# dc25-darknet-dialer-eaglev8_3.net
KiCad netlist of a schematic drawn in EAGLE
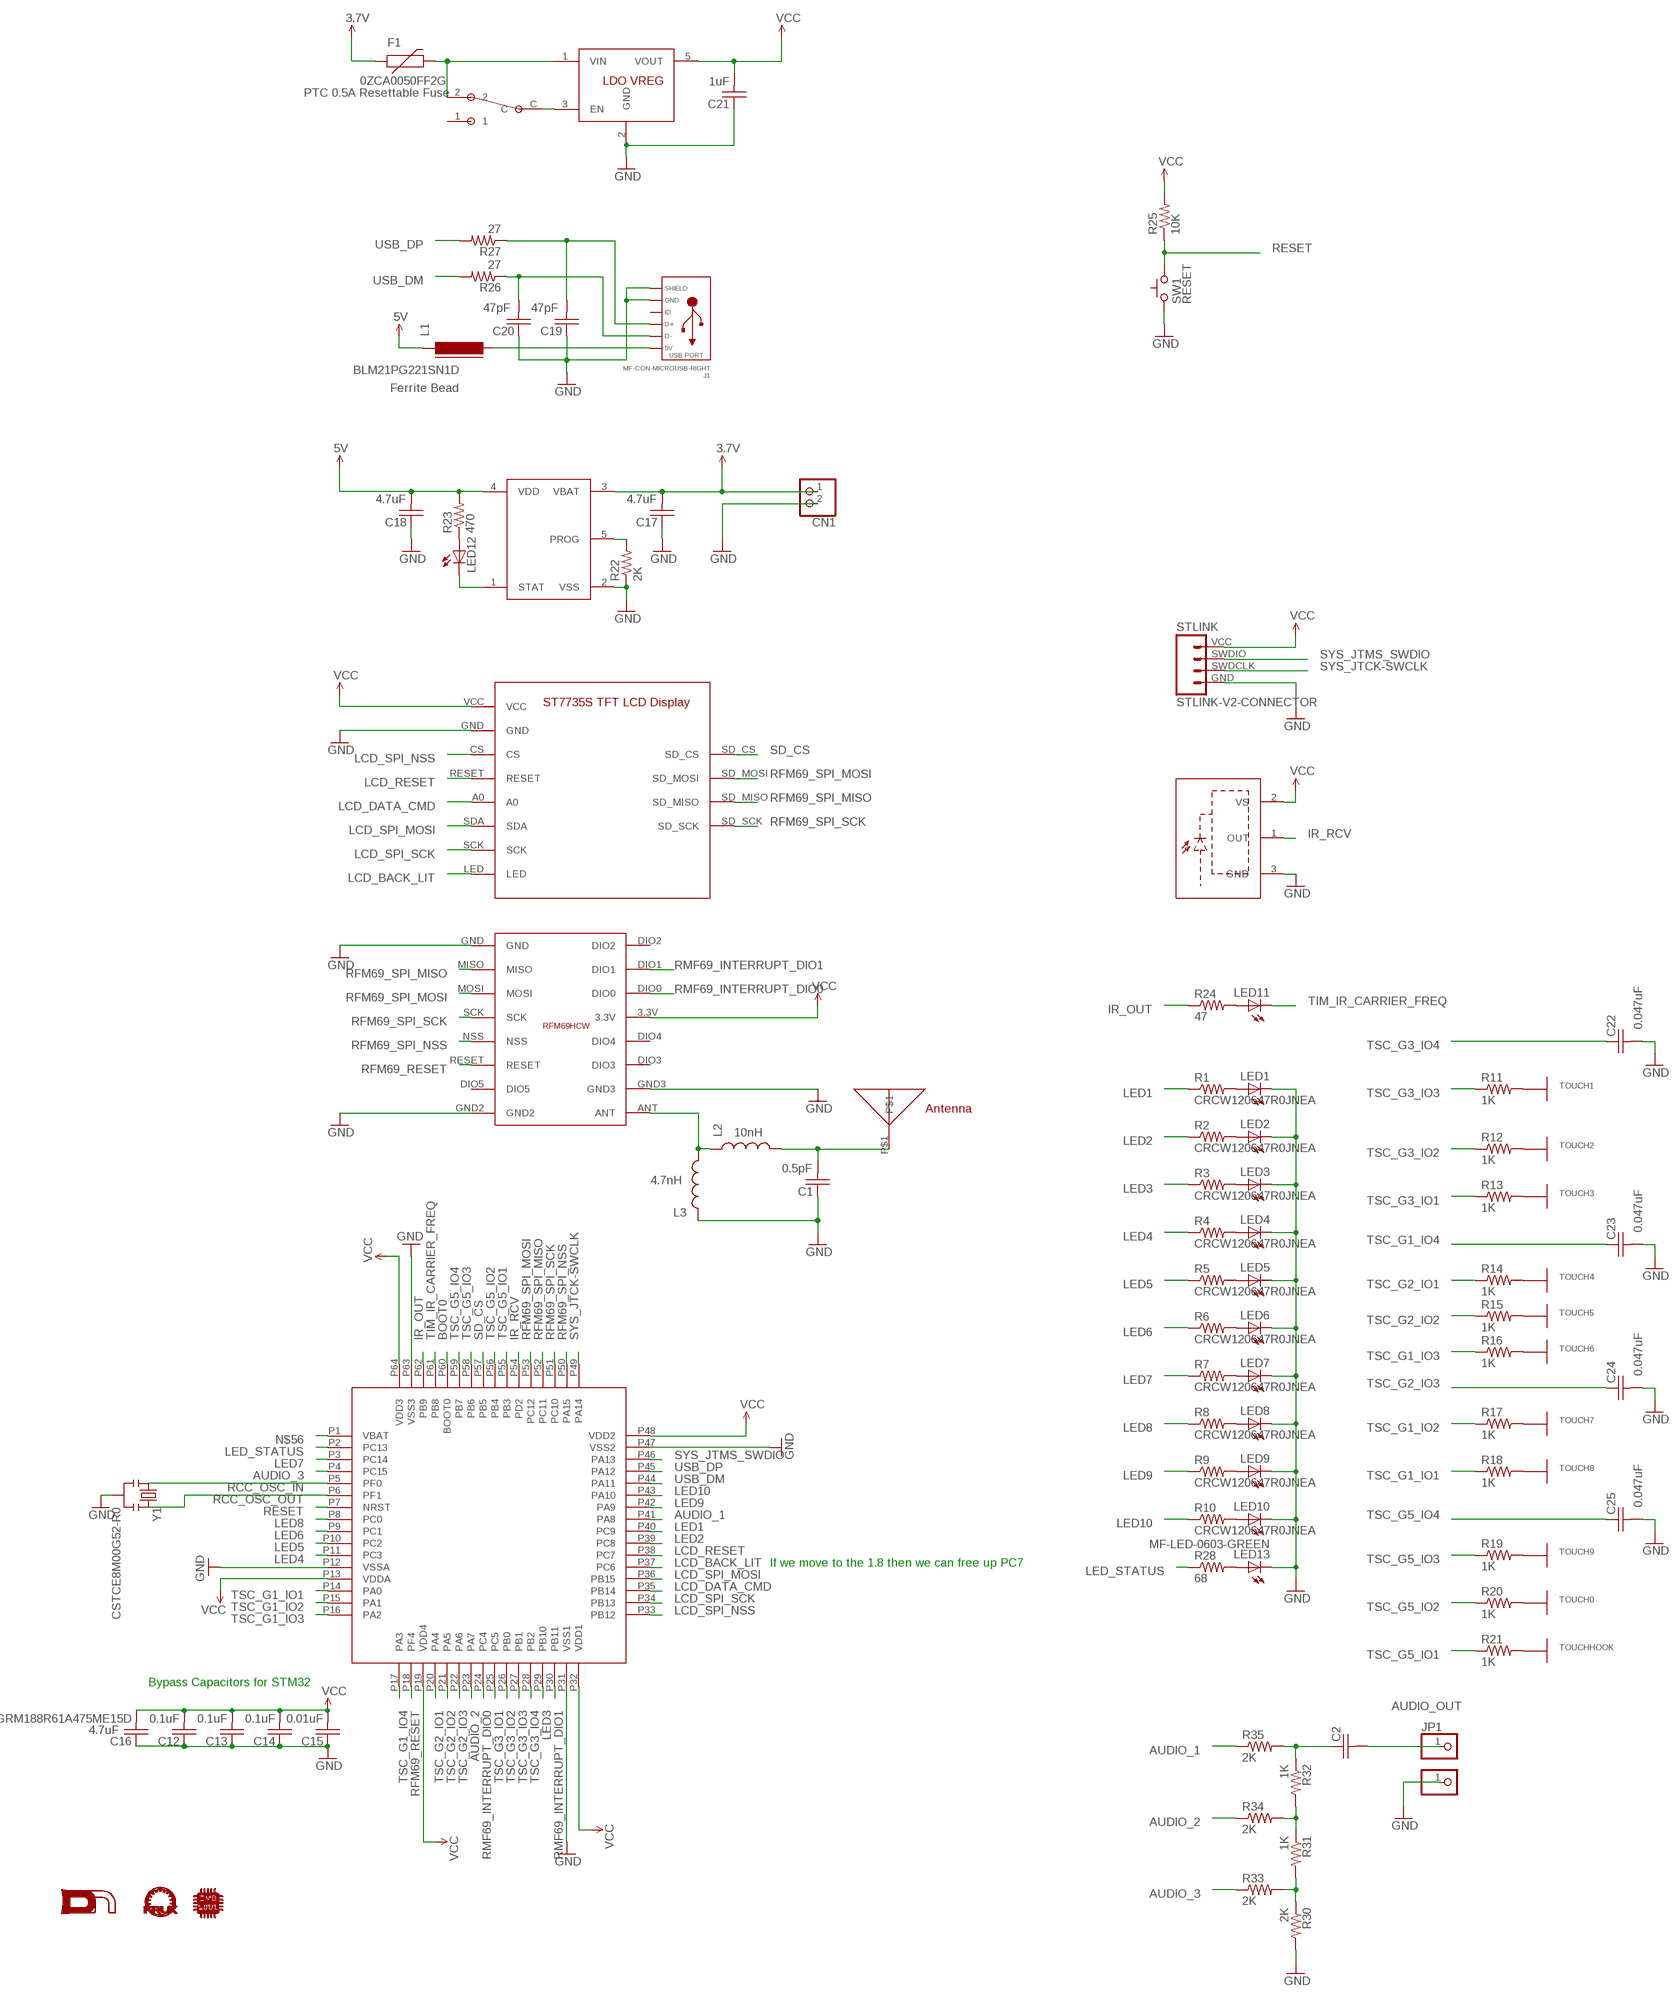
[diagram p0: schematic, sheet 1]

(export (version "E")
  (design (tool "Eeschema 10.0.6"))
  (components
    (comp (ref "C1")
      (value "251R14S0R5BV4T")
      (footprint "eagle-import:C0603")
      (libsource (lib "eagle-import") (part "C-USC0603"))
    )
    (comp (ref "C2")
      (value "GRM188C80G106ME47D")
      (footprint "eagle-import:C0603")
      (libsource (lib "eagle-import") (part "C-USC0603"))
    )
    (comp (ref "C12")
      (value "0.1uF")
      (footprint "eagle-import:C0603")
      (libsource (lib "eagle-import") (part "C-USC0603"))
    )
    (comp (ref "C13")
      (value "0.1uF")
      (footprint "eagle-import:C0603")
      (libsource (lib "eagle-import") (part "C-USC0603"))
    )
    (comp (ref "C14")
      (value "0.1uF")
      (footprint "eagle-import:C0603")
      (libsource (lib "eagle-import") (part "C-USC0603"))
    )
    (comp (ref "C15")
      (value "0.01uF")
      (footprint "eagle-import:C0603")
      (libsource (lib "eagle-import") (part "C-USC0603"))
    )
    (comp (ref "C16")
      (value "GRM188R61A475ME15D")
      (footprint "eagle-import:C0603")
      (libsource (lib "eagle-import") (part "C-USC0603"))
    )
    (comp (ref "C17")
      (value "GRM188R61A475ME15D")
      (footprint "eagle-import:C0603")
      (libsource (lib "eagle-import") (part "C-USC0603"))
    )
    (comp (ref "C18")
      (value "GRM188R61A475ME15D")
      (footprint "eagle-import:C0603")
      (libsource (lib "eagle-import") (part "C-USC0603"))
    )
    (comp (ref "C19")
      (value "C0603C470J3GACTU")
      (footprint "eagle-import:C0603")
      (libsource (lib "eagle-import") (part "C-USC0603"))
    )
    (comp (ref "C20")
      (value "C0603C470J3GACTU")
      (footprint "eagle-import:C0603")
      (libsource (lib "eagle-import") (part "C-USC0603"))
    )
    (comp (ref "C21")
      (value "1uF")
      (footprint "eagle-import:C0603")
      (libsource (lib "eagle-import") (part "C-USC0603"))
    )
    (comp (ref "C22")
      (value "C0603C473J3RACAUTO")
      (footprint "eagle-import:C0603")
      (libsource (lib "eagle-import") (part "C-USC0603"))
    )
    (comp (ref "C23")
      (value "C0603C473J3RACAUTO")
      (footprint "eagle-import:C0603")
      (libsource (lib "eagle-import") (part "C-USC0603"))
    )
    (comp (ref "C24")
      (value "C0603C473J3RACAUTO")
      (footprint "eagle-import:C0603")
      (libsource (lib "eagle-import") (part "C-USC0603"))
    )
    (comp (ref "C25")
      (value "C0603C473J3RACAUTO")
      (footprint "eagle-import:C0603")
      (libsource (lib "eagle-import") (part "C-USC0603"))
    )
    (comp (ref "CN1")
      (value "JST_2PIN-THM-RA")
      (footprint "eagle-import:JST-PH-2-THM-RA")
      (libsource (lib "eagle-import") (part "JST_2PIN-THM-RA"))
    )
    (comp (ref "F1")
      (value "0ZCA0050FF2G")
      (footprint "eagle-import:PTC-1206")
      (libsource (lib "eagle-import") (part "PTCSMD"))
    )
    (comp (ref "J1")
      (value "MF-CON-MICROUSB-RIGHT")
      (footprint "eagle-import:MICROUSB-RIGHT")
      (fields (field (name "HOUSEPART") "YES"))
      (libsource (lib "eagle-import") (part "USB_MICRO_RIGHT"))
    )
    (comp (ref "JP1")
      (value "PINHD-1X1CB")
      (footprint "eagle-import:1X01-CLEANBIG")
      (libsource (lib "eagle-import") (part "PINHD-1X1CB"))
    )
    (comp (ref "JP2")
      (value "PINHD-1X1CB")
      (footprint "eagle-import:1X01-CLEANBIG")
      (libsource (lib "eagle-import") (part "PINHD-1X1CB"))
    )
    (comp (ref "L1")
      (value "BLM21PG221SN1D")
      (footprint "eagle-import:FB603")
      (libsource (lib "eagle-import") (part "FERRITE-0603"))
    )
    (comp (ref "L2")
      (value "CI160808-10NJ")
      (footprint "eagle-import:0603")
      (libsource (lib "eagle-import") (part "INDUCTOR0603"))
    )
    (comp (ref "L3")
      (value "CI160808-4N7D")
      (footprint "eagle-import:0603")
      (libsource (lib "eagle-import") (part "INDUCTOR0603"))
    )
    (comp (ref "LED1")
      (value "LEDREVERSEMOUNT_NOPASTE")
      (footprint "eagle-import:GULLWING_LED_NOPASTE")
      (libsource (lib "eagle-import") (part "LEDREVERSEMOUNT_NOPASTE"))
    )
    (comp (ref "LED2")
      (value "LEDREVERSEMOUNT_NOPASTE")
      (footprint "eagle-import:GULLWING_LED_NOPASTE")
      (libsource (lib "eagle-import") (part "LEDREVERSEMOUNT_NOPASTE"))
    )
    (comp (ref "LED3")
      (value "LEDREVERSEMOUNT_NOPASTE")
      (footprint "eagle-import:GULLWING_LED_NOPASTE")
      (libsource (lib "eagle-import") (part "LEDREVERSEMOUNT_NOPASTE"))
    )
    (comp (ref "LED4")
      (value "LEDREVERSEMOUNT_NOPASTE")
      (footprint "eagle-import:GULLWING_LED_NOPASTE")
      (libsource (lib "eagle-import") (part "LEDREVERSEMOUNT_NOPASTE"))
    )
    (comp (ref "LED5")
      (value "LEDREVERSEMOUNT_NOPASTE")
      (footprint "eagle-import:GULLWING_LED_NOPASTE")
      (libsource (lib "eagle-import") (part "LEDREVERSEMOUNT_NOPASTE"))
    )
    (comp (ref "LED6")
      (value "LEDREVERSEMOUNT_NOPASTE")
      (footprint "eagle-import:GULLWING_LED_NOPASTE")
      (libsource (lib "eagle-import") (part "LEDREVERSEMOUNT_NOPASTE"))
    )
    (comp (ref "LED7")
      (value "LEDREVERSEMOUNT_NOPASTE")
      (footprint "eagle-import:GULLWING_LED_NOPASTE")
      (libsource (lib "eagle-import") (part "LEDREVERSEMOUNT_NOPASTE"))
    )
    (comp (ref "LED8")
      (value "LEDREVERSEMOUNT_NOPASTE")
      (footprint "eagle-import:GULLWING_LED_NOPASTE")
      (libsource (lib "eagle-import") (part "LEDREVERSEMOUNT_NOPASTE"))
    )
    (comp (ref "LED9")
      (value "LEDREVERSEMOUNT_NOPASTE")
      (footprint "eagle-import:GULLWING_LED_NOPASTE")
      (libsource (lib "eagle-import") (part "LEDREVERSEMOUNT_NOPASTE"))
    )
    (comp (ref "LED10")
      (value "LEDREVERSEMOUNT_NOPASTE")
      (footprint "eagle-import:GULLWING_LED_NOPASTE")
      (libsource (lib "eagle-import") (part "LEDREVERSEMOUNT_NOPASTE"))
    )
    (comp (ref "LED11")
      (value "LED5MM")
      (footprint "eagle-import:LED5MM")
      (libsource (lib "eagle-import") (part "LED5MM"))
    )
    (comp (ref "LED12")
      (value "MF-LED-0603-GREEN")
      (footprint "eagle-import:LED-0603")
      (libsource (lib "eagle-import") (part "LED0603"))
    )
    (comp (ref "LED13")
      (value "MF-LED-0603-GREEN")
      (footprint "eagle-import:LED-0603")
      (libsource (lib "eagle-import") (part "LED0603"))
    )
    (comp (ref "R1")
      (value "CRCW120647R0JNEA")
      (footprint "eagle-import:1206")
      (libsource (lib "eagle-import") (part "RESISTOR1206"))
    )
    (comp (ref "R2")
      (value "CRCW120647R0JNEA")
      (footprint "eagle-import:1206")
      (libsource (lib "eagle-import") (part "RESISTOR1206"))
    )
    (comp (ref "R3")
      (value "CRCW120647R0JNEA")
      (footprint "eagle-import:1206")
      (libsource (lib "eagle-import") (part "RESISTOR1206"))
    )
    (comp (ref "R4")
      (value "CRCW120647R0JNEA")
      (footprint "eagle-import:1206")
      (libsource (lib "eagle-import") (part "RESISTOR1206"))
    )
    (comp (ref "R5")
      (value "CRCW120647R0JNEA")
      (footprint "eagle-import:1206")
      (libsource (lib "eagle-import") (part "RESISTOR1206"))
    )
    (comp (ref "R6")
      (value "CRCW120647R0JNEA")
      (footprint "eagle-import:1206")
      (libsource (lib "eagle-import") (part "RESISTOR1206"))
    )
    (comp (ref "R7")
      (value "CRCW120647R0JNEA")
      (footprint "eagle-import:1206")
      (libsource (lib "eagle-import") (part "RESISTOR1206"))
    )
    (comp (ref "R8")
      (value "CRCW120647R0JNEA")
      (footprint "eagle-import:1206")
      (libsource (lib "eagle-import") (part "RESISTOR1206"))
    )
    (comp (ref "R9")
      (value "CRCW120647R0JNEA")
      (footprint "eagle-import:1206")
      (libsource (lib "eagle-import") (part "RESISTOR1206"))
    )
    (comp (ref "R10")
      (value "CRCW120647R0JNEA")
      (footprint "eagle-import:1206")
      (libsource (lib "eagle-import") (part "RESISTOR1206"))
    )
    (comp (ref "R11")
      (value "1K")
      (footprint "eagle-import:0603-RES")
      (libsource (lib "eagle-import") (part "RESISTOR0603-RES"))
    )
    (comp (ref "R12")
      (value "1K")
      (footprint "eagle-import:0603-RES")
      (libsource (lib "eagle-import") (part "RESISTOR0603-RES"))
    )
    (comp (ref "R13")
      (value "1K")
      (footprint "eagle-import:0603-RES")
      (libsource (lib "eagle-import") (part "RESISTOR0603-RES"))
    )
    (comp (ref "R14")
      (value "1K")
      (footprint "eagle-import:0603-RES")
      (libsource (lib "eagle-import") (part "RESISTOR0603-RES"))
    )
    (comp (ref "R15")
      (value "1K")
      (footprint "eagle-import:0603-RES")
      (libsource (lib "eagle-import") (part "RESISTOR0603-RES"))
    )
    (comp (ref "R16")
      (value "1K")
      (footprint "eagle-import:0603-RES")
      (libsource (lib "eagle-import") (part "RESISTOR0603-RES"))
    )
    (comp (ref "R17")
      (value "1K")
      (footprint "eagle-import:0603-RES")
      (libsource (lib "eagle-import") (part "RESISTOR0603-RES"))
    )
    (comp (ref "R18")
      (value "1K")
      (footprint "eagle-import:0603-RES")
      (libsource (lib "eagle-import") (part "RESISTOR0603-RES"))
    )
    (comp (ref "R19")
      (value "1K")
      (footprint "eagle-import:0603-RES")
      (libsource (lib "eagle-import") (part "RESISTOR0603-RES"))
    )
    (comp (ref "R20")
      (value "1K")
      (footprint "eagle-import:0603-RES")
      (libsource (lib "eagle-import") (part "RESISTOR0603-RES"))
    )
    (comp (ref "R21")
      (value "1K")
      (footprint "eagle-import:0603-RES")
      (libsource (lib "eagle-import") (part "RESISTOR0603-RES"))
    )
    (comp (ref "R22")
      (value "2K")
      (footprint "eagle-import:0603-RES")
      (libsource (lib "eagle-import") (part "RESISTOR0603-RES"))
    )
    (comp (ref "R23")
      (value "470")
      (footprint "eagle-import:0603-RES")
      (libsource (lib "eagle-import") (part "RESISTOR0603-RES"))
    )
    (comp (ref "R24")
      (value "47")
      (footprint "eagle-import:0207_7")
      (libsource (lib "eagle-import") (part "R-US_0207/7"))
    )
    (comp (ref "R25")
      (value "10K")
      (footprint "eagle-import:0603-RES")
      (libsource (lib "eagle-import") (part "RESISTOR0603-RES"))
    )
    (comp (ref "R26")
      (value "27")
      (footprint "eagle-import:0603-RES")
      (libsource (lib "eagle-import") (part "RESISTOR0603-RES"))
    )
    (comp (ref "R27")
      (value "27")
      (footprint "eagle-import:0603-RES")
      (libsource (lib "eagle-import") (part "RESISTOR0603-RES"))
    )
    (comp (ref "R28")
      (value "68")
      (footprint "eagle-import:0603-RES")
      (libsource (lib "eagle-import") (part "RESISTOR0603-RES"))
    )
    (comp (ref "R30")
      (value "2K")
      (footprint "eagle-import:0603-RES")
      (libsource (lib "eagle-import") (part "RESISTOR0603-RES"))
    )
    (comp (ref "R31")
      (value "1K")
      (footprint "eagle-import:0603-RES")
      (libsource (lib "eagle-import") (part "RESISTOR0603-RES"))
    )
    (comp (ref "R32")
      (value "1K")
      (footprint "eagle-import:0603-RES")
      (libsource (lib "eagle-import") (part "RESISTOR0603-RES"))
    )
    (comp (ref "R33")
      (value "2K")
      (footprint "eagle-import:0603-RES")
      (libsource (lib "eagle-import") (part "RESISTOR0603-RES"))
    )
    (comp (ref "R34")
      (value "2K")
      (footprint "eagle-import:0603-RES")
      (libsource (lib "eagle-import") (part "RESISTOR0603-RES"))
    )
    (comp (ref "R35")
      (value "2K")
      (footprint "eagle-import:0603-RES")
      (libsource (lib "eagle-import") (part "RESISTOR0603-RES"))
    )
    (comp (ref "STLINK")
      (value "STLINK-V2-CONNECTOR")
      (footprint "eagle-import:1X04")
      (libsource (lib "eagle-import") (part "STLINK-V2-CONNECTOR"))
    )
    (comp (ref "SW1")
      (value "RESET")
      (footprint "eagle-import:TACTILE-2PIN-NARROW")
      (libsource (lib "eagle-import") (part "SWITCH_TACTILETACTILE-2PIN-NARROW"))
    )
    (comp (ref "TOUCH0")
      (value "CAP_TOUCH0")
      (footprint "eagle-import:CAP_TOUCH_PAD_0")
      (libsource (lib "eagle-import") (part "CAP_TOUCH0"))
    )
    (comp (ref "TOUCH1")
      (value "CAP_TOUCH1")
      (footprint "eagle-import:CAP_TOUCH_PAD_1")
      (libsource (lib "eagle-import") (part "CAP_TOUCH1"))
    )
    (comp (ref "TOUCH2")
      (value "CAP_TOUCH2")
      (footprint "eagle-import:CAP_TOUCH_PAD_2")
      (libsource (lib "eagle-import") (part "CAP_TOUCH2"))
    )
    (comp (ref "TOUCH3")
      (value "CAP_TOUCH3")
      (footprint "eagle-import:CAP_TOUCH_PAD_3")
      (libsource (lib "eagle-import") (part "CAP_TOUCH3"))
    )
    (comp (ref "TOUCH4")
      (value "CAP_TOUCH4")
      (footprint "eagle-import:CAP_TOUCH_PAD_4")
      (libsource (lib "eagle-import") (part "CAP_TOUCH4"))
    )
    (comp (ref "TOUCH5")
      (value "CAP_TOUCH5")
      (footprint "eagle-import:CAP_TOUCH_PAD_5")
      (libsource (lib "eagle-import") (part "CAP_TOUCH5"))
    )
    (comp (ref "TOUCH6")
      (value "CAP_TOUCH6")
      (footprint "eagle-import:CAP_TOUCH_PAD_6")
      (libsource (lib "eagle-import") (part "CAP_TOUCH6"))
    )
    (comp (ref "TOUCH7")
      (value "CAP_TOUCH7")
      (footprint "eagle-import:CAP_TOUCH_PAD_7")
      (libsource (lib "eagle-import") (part "CAP_TOUCH7"))
    )
    (comp (ref "TOUCH8")
      (value "CAP_TOUCH8")
      (footprint "eagle-import:CAP_TOUCH_PAD_8")
      (libsource (lib "eagle-import") (part "CAP_TOUCH8"))
    )
    (comp (ref "TOUCH9")
      (value "CAP_TOUCH9")
      (footprint "eagle-import:CAP_TOUCH_PAD_9")
      (libsource (lib "eagle-import") (part "CAP_TOUCH9"))
    )
    (comp (ref "TOUCHHOOK")
      (value "CAP_TOUCHHOOK")
      (footprint "eagle-import:CAP_TOUCH_PAD_HOOK")
      (libsource (lib "eagle-import") (part "CAP_TOUCHHOOK"))
    )
    (comp (ref "U$1")
      (value "DN_LOGODC25")
      (footprint "eagle-import:DARKNET_LOGO_DC25")
      (libsource (lib "eagle-import") (part "DN_LOGODC25"))
    )
    (comp (ref "U$2")
      (value "STM32F302RBT6")
      (footprint "eagle-import:LQFP64")
      (libsource (lib "eagle-import") (part "STM32F302XC"))
    )
    (comp (ref "U$11")
      (value "SWITCH_SPDT")
      (footprint "eagle-import:SPDT_SSAJ120100")
      (libsource (lib "eagle-import") (part "SWITCH_SPDT"))
    )
    (comp (ref "U$12")
      (value "KRUX_LOGO")
      (footprint "eagle-import:KRUX_LOGO")
      (libsource (lib "eagle-import") (part "KRUX_LOGO"))
    )
    (comp (ref "U$15")
      (value "RFM69HCWRFM69HCWSMDNOPASTE")
      (footprint "eagle-import:16PIN-PCB-SMD-NOPASTE")
      (libsource (lib "eagle-import") (part "RFM69HCWRFM69HCWSMDNOPASTE"))
    )
    (comp (ref "U$21")
      (value "0915AT43A0026E")
      (footprint "eagle-import:CHIP_ANTENNA_1.8X8MM")
      (libsource (lib "eagle-import") (part "CHIP_ANTENNA"))
    )
    (comp (ref "U$22")
      (value "ST7735S_LCD_MODULE")
      (footprint "eagle-import:ST7735S_LCD_DISPLAY")
      (libsource (lib "eagle-import") (part "ST7735S_LCD_MODULE"))
    )
    (comp (ref "U$23")
      (value "CMD_C0DE_LOGO")
      (footprint "eagle-import:CMD_C0DE_LOGO")
      (libsource (lib "eagle-import") (part "CMD_C0DE_LOGO"))
    )
    (comp (ref "U1")
      (value "BU33SD5WG-TR")
      (footprint "eagle-import:SOT23-5")
      (libsource (lib "eagle-import") (part "TLV702"))
    )
    (comp (ref "U2")
      (value "MCP73831T-5ACI/OT")
      (footprint "eagle-import:SOT23-5")
      (libsource (lib "eagle-import") (part "DS21984E"))
    )
    (comp (ref "U3")
      (value "SOP22FLAT")
      (footprint "eagle-import:IR-MODULE_FLAT")
      (libsource (lib "eagle-import") (part "SOP22FLAT"))
    )
    (comp (ref "Y1")
      (value "CSTCE8M00G52-R0")
      (footprint "eagle-import:RESONATOR-SMD")
      (libsource (lib "eagle-import") (part "RESONATORSMD"))
    )
  )
  (nets
    (net (code "1") (name "/AUDIO_1") (class "Default")
      (node (ref "R35") (pin "1") (pinfunction "1_1") (pintype "passive"))
      (node (ref "U$2") (pin "P41") (pinfunction "PA8_P41") (pintype "bidirectional"))
    )
    (net (code "2") (name "/AUDIO_2") (class "Default")
      (node (ref "R34") (pin "1") (pinfunction "1_1") (pintype "passive"))
      (node (ref "U$2") (pin "P23") (pinfunction "PA7_P23") (pintype "bidirectional"))
    )
    (net (code "3") (name "/AUDIO_3") (class "Default")
      (node (ref "R33") (pin "1") (pinfunction "1_1") (pintype "passive"))
      (node (ref "U$2") (pin "P4") (pinfunction "PC15_P4") (pintype "bidirectional"))
    )
    (net (code "4") (name "/AUDIO_OUT") (class "Default")
      (node (ref "C2") (pin "2") (pinfunction "2_2") (pintype "passive"))
      (node (ref "JP1") (pin "1") (pinfunction "1_1") (pintype "passive"))
    )
    (net (code "5") (name "/BOOT0") (class "Default")
      (node (ref "U$2") (pin "P60") (pinfunction "BOOT0_P60") (pintype "bidirectional"))
    )
    (net (code "6") (name "/IR_OUT") (class "Default")
      (node (ref "R24") (pin "1") (pinfunction "1_1") (pintype "passive"))
      (node (ref "U$2") (pin "P62") (pinfunction "PB9_P62") (pintype "bidirectional"))
    )
    (net (code "7") (name "/IR_RCV") (class "Default")
      (node (ref "U$2") (pin "P54") (pinfunction "PD2_P54") (pintype "bidirectional"))
      (node (ref "U3") (pin "1") (pinfunction "OUT_1") (pintype "bidirectional"))
    )
    (net (code "8") (name "/LCD_BACK_LIT") (class "Default")
      (node (ref "U$2") (pin "P37") (pinfunction "PC6_P37") (pintype "bidirectional"))
      (node (ref "U$22") (pin "LED") (pinfunction "LED_LED") (pintype "bidirectional"))
    )
    (net (code "9") (name "/LCD_DATA_CMD") (class "Default")
      (node (ref "U$2") (pin "P35") (pinfunction "PB14_P35") (pintype "bidirectional"))
      (node (ref "U$22") (pin "A0") (pinfunction "A0_A0") (pintype "bidirectional"))
    )
    (net (code "10") (name "/LCD_RESET") (class "Default")
      (node (ref "U$2") (pin "P38") (pinfunction "PC7_P38") (pintype "bidirectional"))
      (node (ref "U$22") (pin "RESET") (pinfunction "RESET_RESET") (pintype "bidirectional"))
    )
    (net (code "11") (name "/LCD_SPI_MOSI") (class "Default")
      (node (ref "U$2") (pin "P36") (pinfunction "PB15_P36") (pintype "bidirectional"))
      (node (ref "U$22") (pin "SDA") (pinfunction "SDA_SDA") (pintype "bidirectional"))
    )
    (net (code "12") (name "/LCD_SPI_NSS") (class "Default")
      (node (ref "U$2") (pin "P33") (pinfunction "PB12_P33") (pintype "bidirectional"))
      (node (ref "U$22") (pin "CS") (pinfunction "CS_CS") (pintype "bidirectional"))
    )
    (net (code "13") (name "/LCD_SPI_SCK") (class "Default")
      (node (ref "U$2") (pin "P34") (pinfunction "PB13_P34") (pintype "bidirectional"))
      (node (ref "U$22") (pin "SCK") (pinfunction "SCK_SCK") (pintype "bidirectional"))
    )
    (net (code "14") (name "/LED1") (class "Default")
      (node (ref "R1") (pin "1") (pinfunction "1_1") (pintype "passive"))
      (node (ref "U$2") (pin "P40") (pinfunction "PC9_P40") (pintype "bidirectional"))
    )
    (net (code "15") (name "/LED2") (class "Default")
      (node (ref "R2") (pin "1") (pinfunction "1_1") (pintype "passive"))
      (node (ref "U$2") (pin "P39") (pinfunction "PC8_P39") (pintype "bidirectional"))
    )
    (net (code "16") (name "/LED3") (class "Default")
      (node (ref "R3") (pin "1") (pinfunction "1_1") (pintype "passive"))
      (node (ref "U$2") (pin "P29") (pinfunction "PB10_P29") (pintype "bidirectional"))
    )
    (net (code "17") (name "/LED4") (class "Default")
      (node (ref "R4") (pin "1") (pinfunction "1_1") (pintype "passive"))
      (node (ref "U$2") (pin "P11") (pinfunction "PC3_P11") (pintype "bidirectional"))
    )
    (net (code "18") (name "/LED5") (class "Default")
      (node (ref "R5") (pin "1") (pinfunction "1_1") (pintype "passive"))
      (node (ref "U$2") (pin "P10") (pinfunction "PC2_P10") (pintype "bidirectional"))
    )
    (net (code "19") (name "/LED6") (class "Default")
      (node (ref "R6") (pin "1") (pinfunction "1_1") (pintype "passive"))
      (node (ref "U$2") (pin "P9") (pinfunction "PC1_P9") (pintype "bidirectional"))
    )
    (net (code "20") (name "/LED7") (class "Default")
      (node (ref "R7") (pin "1") (pinfunction "1_1") (pintype "passive"))
      (node (ref "U$2") (pin "P3") (pinfunction "PC14_P3") (pintype "bidirectional"))
    )
    (net (code "21") (name "/LED8") (class "Default")
      (node (ref "R8") (pin "1") (pinfunction "1_1") (pintype "passive"))
      (node (ref "U$2") (pin "P8") (pinfunction "PC0_P8") (pintype "bidirectional"))
    )
    (net (code "22") (name "/LED9") (class "Default")
      (node (ref "R9") (pin "1") (pinfunction "1_1") (pintype "passive"))
      (node (ref "U$2") (pin "P42") (pinfunction "PA9_P42") (pintype "bidirectional"))
    )
    (net (code "23") (name "/LED10") (class "Default")
      (node (ref "R10") (pin "1") (pinfunction "1_1") (pintype "passive"))
      (node (ref "U$2") (pin "P43") (pinfunction "PA10_P43") (pintype "bidirectional"))
    )
    (net (code "24") (name "/LED_STATUS") (class "Default")
      (node (ref "R28") (pin "1") (pinfunction "1_1") (pintype "passive"))
      (node (ref "U$2") (pin "P2") (pinfunction "PC13_P2") (pintype "bidirectional"))
    )
    (net (code "25") (name "/N$56") (class "Default")
      (node (ref "U$2") (pin "P1") (pinfunction "VBAT_P1") (pintype "bidirectional"))
    )
    (net (code "26") (name "/RCC_OSC_IN") (class "Default")
      (node (ref "U$2") (pin "P5") (pinfunction "PF0_P5") (pintype "bidirectional"))
      (node (ref "Y1") (pin "1") (pinfunction "1_1") (pintype "passive"))
    )
    (net (code "27") (name "/RCC_OSC_OUT") (class "Default")
      (node (ref "U$2") (pin "P6") (pinfunction "PF1_P6") (pintype "bidirectional"))
      (node (ref "Y1") (pin "3") (pinfunction "3_3") (pintype "passive"))
    )
    (net (code "28") (name "/RESET") (class "Default")
      (node (ref "R25") (pin "1") (pinfunction "1_1") (pintype "passive"))
      (node (ref "SW1") (pin "P$1") (pinfunction "A_P$1") (pintype "passive"))
      (node (ref "U$2") (pin "P7") (pinfunction "NRST_P7") (pintype "bidirectional"))
    )
    (net (code "29") (name "/RFM69_RESET") (class "Default")
      (node (ref "U$15") (pin "RESET") (pinfunction "RESET_RESET") (pintype "bidirectional"))
      (node (ref "U$2") (pin "P18") (pinfunction "PF4_P18") (pintype "bidirectional"))
    )
    (net (code "30") (name "/RFM69_SPI_MISO") (class "Default")
      (node (ref "U$15") (pin "MISO") (pinfunction "MISO_MISO") (pintype "bidirectional"))
      (node (ref "U$2") (pin "P52") (pinfunction "PC11_P52") (pintype "bidirectional"))
      (node (ref "U$22") (pin "SD_MISO") (pinfunction "SD_MISO_SD_MISO") (pintype "bidirectional"))
    )
    (net (code "31") (name "/RFM69_SPI_MOSI") (class "Default")
      (node (ref "U$15") (pin "MOSI") (pinfunction "MOSI_MOSI") (pintype "bidirectional"))
      (node (ref "U$2") (pin "P53") (pinfunction "PC12_P53") (pintype "bidirectional"))
      (node (ref "U$22") (pin "SD_MOSI") (pinfunction "SD_MOSI_SD_MOSI") (pintype "bidirectional"))
    )
    (net (code "32") (name "/RFM69_SPI_NSS") (class "Default")
      (node (ref "U$15") (pin "NSS") (pinfunction "NSS_NSS") (pintype "bidirectional"))
      (node (ref "U$2") (pin "P50") (pinfunction "PA15_P50") (pintype "bidirectional"))
    )
    (net (code "33") (name "/RFM69_SPI_SCK") (class "Default")
      (node (ref "U$15") (pin "SCK") (pinfunction "SCK_SCK") (pintype "bidirectional"))
      (node (ref "U$2") (pin "P51") (pinfunction "PC10_P51") (pintype "bidirectional"))
      (node (ref "U$22") (pin "SD_SCK") (pinfunction "SD_SCK_SD_SCK") (pintype "bidirectional"))
    )
    (net (code "34") (name "/RMF69_INTERRUPT_DIO0") (class "Default")
      (node (ref "U$15") (pin "DIO0") (pinfunction "DIO0_DIO0") (pintype "bidirectional"))
      (node (ref "U$2") (pin "P24") (pinfunction "PC4_P24") (pintype "bidirectional"))
    )
    (net (code "35") (name "/RMF69_INTERRUPT_DIO1") (class "Default")
      (node (ref "U$15") (pin "DIO1") (pinfunction "DIO1_DIO1") (pintype "bidirectional"))
      (node (ref "U$2") (pin "P30") (pinfunction "PB11_P30") (pintype "bidirectional"))
    )
    (net (code "36") (name "/SD_CS") (class "Default")
      (node (ref "U$2") (pin "P57") (pinfunction "PB5_P57") (pintype "bidirectional"))
      (node (ref "U$22") (pin "SD_CS") (pinfunction "SD_CS_SD_CS") (pintype "bidirectional"))
    )
    (net (code "37") (name "/SYS_JTCK-SWCLK") (class "Default")
      (node (ref "STLINK") (pin "SWDCLK") (pinfunction "SWDCLK_SWDCLK") (pintype "input"))
      (node (ref "U$2") (pin "P49") (pinfunction "PA14_P49") (pintype "bidirectional"))
    )
    (net (code "38") (name "/SYS_JTMS_SWDIO") (class "Default")
      (node (ref "STLINK") (pin "SWDIO") (pinfunction "SWDIO_SWDIO") (pintype "bidirectional"))
      (node (ref "U$2") (pin "P46") (pinfunction "PA13_P46") (pintype "bidirectional"))
    )
    (net (code "39") (name "/TIM_IR_CARRIER_FREQ") (class "Default")
      (node (ref "LED11") (pin "K") (pinfunction "C_K") (pintype "output"))
      (node (ref "U$2") (pin "P61") (pinfunction "PB8_P61") (pintype "bidirectional"))
    )
    (net (code "40") (name "/TSC_G1_IO1") (class "Default")
      (node (ref "R18") (pin "1") (pinfunction "1_1") (pintype "passive"))
      (node (ref "U$2") (pin "P14") (pinfunction "PA0_P14") (pintype "bidirectional"))
    )
    (net (code "41") (name "/TSC_G1_IO2") (class "Default")
      (node (ref "R17") (pin "1") (pinfunction "1_1") (pintype "passive"))
      (node (ref "U$2") (pin "P15") (pinfunction "PA1_P15") (pintype "bidirectional"))
    )
    (net (code "42") (name "/TSC_G1_IO3") (class "Default")
      (node (ref "R16") (pin "1") (pinfunction "1_1") (pintype "passive"))
      (node (ref "U$2") (pin "P16") (pinfunction "PA2_P16") (pintype "bidirectional"))
    )
    (net (code "43") (name "/TSC_G1_IO4") (class "Default")
      (node (ref "C23") (pin "1") (pinfunction "1_1") (pintype "passive"))
      (node (ref "U$2") (pin "P17") (pinfunction "PA3_P17") (pintype "bidirectional"))
    )
    (net (code "44") (name "/TSC_G2_IO1") (class "Default")
      (node (ref "R14") (pin "1") (pinfunction "1_1") (pintype "passive"))
      (node (ref "U$2") (pin "P20") (pinfunction "PA4_P20") (pintype "bidirectional"))
    )
    (net (code "45") (name "/TSC_G2_IO2") (class "Default")
      (node (ref "R15") (pin "1") (pinfunction "1_1") (pintype "passive"))
      (node (ref "U$2") (pin "P21") (pinfunction "PA5_P21") (pintype "bidirectional"))
    )
    (net (code "46") (name "/TSC_G2_IO3") (class "Default")
      (node (ref "C24") (pin "1") (pinfunction "1_1") (pintype "passive"))
      (node (ref "U$2") (pin "P22") (pinfunction "PA6_P22") (pintype "bidirectional"))
    )
    (net (code "47") (name "/TSC_G3_IO1") (class "Default")
      (node (ref "R13") (pin "1") (pinfunction "1_1") (pintype "passive"))
      (node (ref "U$2") (pin "P25") (pinfunction "PC5_P25") (pintype "bidirectional"))
    )
    (net (code "48") (name "/TSC_G3_IO2") (class "Default")
      (node (ref "R12") (pin "1") (pinfunction "1_1") (pintype "passive"))
      (node (ref "U$2") (pin "P26") (pinfunction "PB0_P26") (pintype "bidirectional"))
    )
    (net (code "49") (name "/TSC_G3_IO3") (class "Default")
      (node (ref "R11") (pin "1") (pinfunction "1_1") (pintype "passive"))
      (node (ref "U$2") (pin "P27") (pinfunction "PB1_P27") (pintype "bidirectional"))
    )
    (net (code "50") (name "/TSC_G3_IO4") (class "Default")
      (node (ref "C22") (pin "1") (pinfunction "1_1") (pintype "passive"))
      (node (ref "U$2") (pin "P28") (pinfunction "PB2_P28") (pintype "bidirectional"))
    )
    (net (code "51") (name "/TSC_G5_IO1") (class "Default")
      (node (ref "R21") (pin "1") (pinfunction "1_1") (pintype "passive"))
      (node (ref "U$2") (pin "P55") (pinfunction "PB3_P55") (pintype "bidirectional"))
    )
    (net (code "52") (name "/TSC_G5_IO2") (class "Default")
      (node (ref "R20") (pin "1") (pinfunction "1_1") (pintype "passive"))
      (node (ref "U$2") (pin "P56") (pinfunction "PB4_P56") (pintype "bidirectional"))
    )
    (net (code "53") (name "/TSC_G5_IO3") (class "Default")
      (node (ref "R19") (pin "1") (pinfunction "1_1") (pintype "passive"))
      (node (ref "U$2") (pin "P58") (pinfunction "PB6_P58") (pintype "bidirectional"))
    )
    (net (code "54") (name "/TSC_G5_IO4") (class "Default")
      (node (ref "C25") (pin "1") (pinfunction "1_1") (pintype "passive"))
      (node (ref "U$2") (pin "P59") (pinfunction "PB7_P59") (pintype "bidirectional"))
    )
    (net (code "55") (name "/USB_DM") (class "Default")
      (node (ref "R26") (pin "2") (pinfunction "2_2") (pintype "passive"))
      (node (ref "U$2") (pin "P44") (pinfunction "PA11_P44") (pintype "bidirectional"))
    )
    (net (code "56") (name "/USB_DP") (class "Default")
      (node (ref "R27") (pin "2") (pinfunction "2_2") (pintype "passive"))
      (node (ref "U$2") (pin "P45") (pinfunction "PA12_P45") (pintype "bidirectional"))
    )
    (net (code "57") (name "3.7V") (class "Default")
      (node (ref "C17") (pin "2") (pinfunction "2_2") (pintype "passive"))
      (node (ref "CN1") (pin "1") (pinfunction "2_1") (pintype "passive"))
      (node (ref "F1") (pin "1") (pinfunction "1_1") (pintype "bidirectional"))
      (node (ref "U2") (pin "3") (pinfunction "VBAT_3") (pintype "bidirectional"))
    )
    (net (code "58") (name "5V") (class "Default")
      (node (ref "C18") (pin "2") (pinfunction "2_2") (pintype "passive"))
      (node (ref "L1") (pin "1") (pinfunction "1_1") (pintype "passive"))
      (node (ref "R23") (pin "2") (pinfunction "2_2") (pintype "passive"))
      (node (ref "U2") (pin "4") (pinfunction "VDD_4") (pintype "bidirectional"))
    )
    (net (code "59") (name "GND") (class "Default")
      (node (ref "C1") (pin "1") (pinfunction "1_1") (pintype "passive"))
      (node (ref "C12") (pin "1") (pinfunction "1_1") (pintype "passive"))
      (node (ref "C13") (pin "1") (pinfunction "1_1") (pintype "passive"))
      (node (ref "C14") (pin "1") (pinfunction "1_1") (pintype "passive"))
      (node (ref "C15") (pin "1") (pinfunction "1_1") (pintype "passive"))
      (node (ref "C16") (pin "1") (pinfunction "1_1") (pintype "passive"))
      (node (ref "C17") (pin "1") (pinfunction "1_1") (pintype "passive"))
      (node (ref "C18") (pin "1") (pinfunction "1_1") (pintype "passive"))
      (node (ref "C19") (pin "1") (pinfunction "1_1") (pintype "passive"))
      (node (ref "C20") (pin "1") (pinfunction "1_1") (pintype "passive"))
      (node (ref "C21") (pin "1") (pinfunction "1_1") (pintype "passive"))
      (node (ref "C22") (pin "2") (pinfunction "2_2") (pintype "passive"))
      (node (ref "C23") (pin "2") (pinfunction "2_2") (pintype "passive"))
      (node (ref "C24") (pin "2") (pinfunction "2_2") (pintype "passive"))
      (node (ref "C25") (pin "2") (pinfunction "2_2") (pintype "passive"))
      (node (ref "CN1") (pin "2") (pinfunction "1_2") (pintype "passive"))
      (node (ref "J1") (pin "5") (pinfunction "GND_5") (pintype "power_in"))
      (node (ref "J1") (pin "S1") (pinfunction "SLD_S1") (pintype "power_in"))
      (node (ref "J1") (pin "S2") (pinfunction "SLD_S2") (pintype "power_in"))
      (node (ref "J1") (pin "S3") (pinfunction "SLD_S3") (pintype "power_in"))
      (node (ref "J1") (pin "S4") (pinfunction "SLD_S4") (pintype "power_in"))
      (node (ref "J1") (pin "S5") (pinfunction "SLD_S5") (pintype "power_in"))
      (node (ref "J1") (pin "S6") (pinfunction "SLD_S6") (pintype "power_in"))
      (node (ref "JP2") (pin "1") (pinfunction "1_1") (pintype "passive"))
      (node (ref "L3") (pin "1") (pinfunction "1_1") (pintype "passive"))
      (node (ref "LED1") (pin "C") (pinfunction "C_C") (pintype "output"))
      (node (ref "LED10") (pin "C") (pinfunction "C_C") (pintype "output"))
      (node (ref "LED13") (pin "C") (pinfunction "C_C") (pintype "output"))
      (node (ref "LED2") (pin "C") (pinfunction "C_C") (pintype "output"))
      (node (ref "LED3") (pin "C") (pinfunction "C_C") (pintype "output"))
      (node (ref "LED4") (pin "C") (pinfunction "C_C") (pintype "output"))
      (node (ref "LED5") (pin "C") (pinfunction "C_C") (pintype "output"))
      (node (ref "LED6") (pin "C") (pinfunction "C_C") (pintype "output"))
      (node (ref "LED7") (pin "C") (pinfunction "C_C") (pintype "output"))
      (node (ref "LED8") (pin "C") (pinfunction "C_C") (pintype "output"))
      (node (ref "LED9") (pin "C") (pinfunction "C_C") (pintype "output"))
      (node (ref "R22") (pin "1") (pinfunction "1_1") (pintype "passive"))
      (node (ref "R30") (pin "2") (pinfunction "2_2") (pintype "passive"))
      (node (ref "STLINK") (pin "GND") (pinfunction "GND_GND") (pintype "power_in"))
      (node (ref "SW1") (pin "P$2") (pinfunction "C_P$2") (pintype "passive"))
      (node (ref "U$15") (pin "GND") (pinfunction "GND_GND") (pintype "bidirectional"))
      (node (ref "U$15") (pin "GND2") (pinfunction "GND2_GND2") (pintype "bidirectional"))
      (node (ref "U$15") (pin "GND3") (pinfunction "GND3_GND3") (pintype "bidirectional"))
      (node (ref "U$2") (pin "P12") (pinfunction "VSSA_P12") (pintype "bidirectional"))
      (node (ref "U$2") (pin "P31") (pinfunction "VSS1_P31") (pintype "bidirectional"))
      (node (ref "U$2") (pin "P47") (pinfunction "VSS2_P47") (pintype "bidirectional"))
      (node (ref "U$2") (pin "P63") (pinfunction "VSS3_P63") (pintype "bidirectional"))
      (node (ref "U$22") (pin "GND") (pinfunction "GND_GND") (pintype "bidirectional"))
      (node (ref "U1") (pin "2") (pinfunction "GND_2") (pintype "bidirectional"))
      (node (ref "U2") (pin "2") (pinfunction "VSS_2") (pintype "bidirectional"))
      (node (ref "U3") (pin "3") (pinfunction "GND_3") (pintype "bidirectional"))
      (node (ref "Y1") (pin "2") (pinfunction "2_2") (pintype "passive"))
    )
    (net (code "60") (name "Net-(C1-Pad2)") (class "Default")
      (node (ref "C1") (pin "2") (pinfunction "2_2") (pintype "passive"))
      (node (ref "L2") (pin "2") (pinfunction "2_2") (pintype "passive"))
      (node (ref "U$21") (pin "P$1") (pinfunction "P$1_P$1") (pintype "bidirectional"))
    )
    (net (code "61") (name "Net-(C2-Pad1)") (class "Default")
      (node (ref "C2") (pin "1") (pinfunction "1_1") (pintype "passive"))
      (node (ref "R32") (pin "1") (pinfunction "1_1") (pintype "passive"))
      (node (ref "R35") (pin "2") (pinfunction "2_2") (pintype "passive"))
    )
    (net (code "62") (name "Net-(J1-5V)") (class "Default")
      (node (ref "J1") (pin "1") (pinfunction "5V_1") (pintype "power_in"))
      (node (ref "L1") (pin "2") (pinfunction "2_2") (pintype "passive"))
    )
    (net (code "63") (name "Net-(J1-D+)") (class "Default")
      (node (ref "C19") (pin "2") (pinfunction "2_2") (pintype "passive"))
      (node (ref "J1") (pin "3") (pinfunction "D+_3") (pintype "bidirectional"))
      (node (ref "R27") (pin "1") (pinfunction "1_1") (pintype "passive"))
    )
    (net (code "64") (name "Net-(J1-D-)") (class "Default")
      (node (ref "C20") (pin "2") (pinfunction "2_2") (pintype "passive"))
      (node (ref "J1") (pin "2") (pinfunction "D-_2") (pintype "bidirectional"))
      (node (ref "R26") (pin "1") (pinfunction "1_1") (pintype "passive"))
    )
    (net (code "65") (name "Net-(L2-Pad1)") (class "Default")
      (node (ref "L2") (pin "1") (pinfunction "1_1") (pintype "passive"))
      (node (ref "L3") (pin "2") (pinfunction "2_2") (pintype "passive"))
      (node (ref "U$15") (pin "ANT") (pinfunction "ANT_ANT") (pintype "bidirectional"))
    )
    (net (code "66") (name "Net-(LED1-PadA)") (class "Default")
      (node (ref "LED1") (pin "A") (pinfunction "A_A") (pintype "input"))
      (node (ref "R1") (pin "2") (pinfunction "2_2") (pintype "passive"))
    )
    (net (code "67") (name "Net-(LED2-PadA)") (class "Default")
      (node (ref "LED2") (pin "A") (pinfunction "A_A") (pintype "input"))
      (node (ref "R2") (pin "2") (pinfunction "2_2") (pintype "passive"))
    )
    (net (code "68") (name "Net-(LED3-PadA)") (class "Default")
      (node (ref "LED3") (pin "A") (pinfunction "A_A") (pintype "input"))
      (node (ref "R3") (pin "2") (pinfunction "2_2") (pintype "passive"))
    )
    (net (code "69") (name "Net-(LED4-PadA)") (class "Default")
      (node (ref "LED4") (pin "A") (pinfunction "A_A") (pintype "input"))
      (node (ref "R4") (pin "2") (pinfunction "2_2") (pintype "passive"))
    )
    (net (code "70") (name "Net-(LED5-PadA)") (class "Default")
      (node (ref "LED5") (pin "A") (pinfunction "A_A") (pintype "input"))
      (node (ref "R5") (pin "2") (pinfunction "2_2") (pintype "passive"))
    )
    (net (code "71") (name "Net-(LED6-PadA)") (class "Default")
      (node (ref "LED6") (pin "A") (pinfunction "A_A") (pintype "input"))
      (node (ref "R6") (pin "2") (pinfunction "2_2") (pintype "passive"))
    )
    (net (code "72") (name "Net-(LED7-PadA)") (class "Default")
      (node (ref "LED7") (pin "A") (pinfunction "A_A") (pintype "input"))
      (node (ref "R7") (pin "2") (pinfunction "2_2") (pintype "passive"))
    )
    (net (code "73") (name "Net-(LED8-PadA)") (class "Default")
      (node (ref "LED8") (pin "A") (pinfunction "A_A") (pintype "input"))
      (node (ref "R8") (pin "2") (pinfunction "2_2") (pintype "passive"))
    )
    (net (code "74") (name "Net-(LED9-PadA)") (class "Default")
      (node (ref "LED9") (pin "A") (pinfunction "A_A") (pintype "input"))
      (node (ref "R9") (pin "2") (pinfunction "2_2") (pintype "passive"))
    )
    (net (code "75") (name "Net-(LED10-PadA)") (class "Default")
      (node (ref "LED10") (pin "A") (pinfunction "A_A") (pintype "input"))
      (node (ref "R10") (pin "2") (pinfunction "2_2") (pintype "passive"))
    )
    (net (code "76") (name "Net-(LED11-PadA)") (class "Default")
      (node (ref "LED11") (pin "A") (pinfunction "A_A") (pintype "input"))
      (node (ref "R24") (pin "2") (pinfunction "2_2") (pintype "passive"))
    )
    (net (code "77") (name "Net-(LED12-PadA)") (class "Default")
      (node (ref "LED12") (pin "A") (pinfunction "A_A") (pintype "input"))
      (node (ref "R23") (pin "1") (pinfunction "1_1") (pintype "passive"))
    )
    (net (code "78") (name "Net-(LED13-PadA)") (class "Default")
      (node (ref "LED13") (pin "A") (pinfunction "A_A") (pintype "input"))
      (node (ref "R28") (pin "2") (pinfunction "2_2") (pintype "passive"))
    )
    (net (code "79") (name "Net-(R30-Pad1)") (class "Default")
      (node (ref "R30") (pin "1") (pinfunction "1_1") (pintype "passive"))
      (node (ref "R31") (pin "2") (pinfunction "2_2") (pintype "passive"))
      (node (ref "R33") (pin "2") (pinfunction "2_2") (pintype "passive"))
    )
    (net (code "80") (name "Net-(R31-Pad1)") (class "Default")
      (node (ref "R31") (pin "1") (pinfunction "1_1") (pintype "passive"))
      (node (ref "R32") (pin "2") (pinfunction "2_2") (pintype "passive"))
      (node (ref "R34") (pin "2") (pinfunction "2_2") (pintype "passive"))
    )
    (net (code "81") (name "Net-(TOUCH0-TOUCH)") (class "Default")
      (node (ref "R20") (pin "2") (pinfunction "2_2") (pintype "passive"))
      (node (ref "TOUCH0") (pin "PAD") (pinfunction "TOUCH_PAD") (pintype "bidirectional"))
    )
    (net (code "82") (name "Net-(TOUCH1-TOUCH)") (class "Default")
      (node (ref "R11") (pin "2") (pinfunction "2_2") (pintype "passive"))
      (node (ref "TOUCH1") (pin "PAD") (pinfunction "TOUCH_PAD") (pintype "bidirectional"))
    )
    (net (code "83") (name "Net-(TOUCH2-TOUCH)") (class "Default")
      (node (ref "R12") (pin "2") (pinfunction "2_2") (pintype "passive"))
      (node (ref "TOUCH2") (pin "PAD") (pinfunction "TOUCH_PAD") (pintype "bidirectional"))
    )
    (net (code "84") (name "Net-(TOUCH3-TOUCH)") (class "Default")
      (node (ref "R13") (pin "2") (pinfunction "2_2") (pintype "passive"))
      (node (ref "TOUCH3") (pin "PAD") (pinfunction "TOUCH_PAD") (pintype "bidirectional"))
    )
    (net (code "85") (name "Net-(TOUCH4-TOUCH)") (class "Default")
      (node (ref "R14") (pin "2") (pinfunction "2_2") (pintype "passive"))
      (node (ref "TOUCH4") (pin "PAD") (pinfunction "TOUCH_PAD") (pintype "bidirectional"))
    )
    (net (code "86") (name "Net-(TOUCH5-TOUCH)") (class "Default")
      (node (ref "R15") (pin "2") (pinfunction "2_2") (pintype "passive"))
      (node (ref "TOUCH5") (pin "PAD") (pinfunction "TOUCH_PAD") (pintype "bidirectional"))
    )
    (net (code "87") (name "Net-(TOUCH6-TOUCH)") (class "Default")
      (node (ref "R16") (pin "2") (pinfunction "2_2") (pintype "passive"))
      (node (ref "TOUCH6") (pin "PAD") (pinfunction "TOUCH_PAD") (pintype "bidirectional"))
    )
    (net (code "88") (name "Net-(TOUCH7-TOUCH)") (class "Default")
      (node (ref "R17") (pin "2") (pinfunction "2_2") (pintype "passive"))
      (node (ref "TOUCH7") (pin "PAD") (pinfunction "TOUCH_PAD") (pintype "bidirectional"))
    )
    (net (code "89") (name "Net-(TOUCH8-TOUCH)") (class "Default")
      (node (ref "R18") (pin "2") (pinfunction "2_2") (pintype "passive"))
      (node (ref "TOUCH8") (pin "PAD") (pinfunction "TOUCH_PAD") (pintype "bidirectional"))
    )
    (net (code "90") (name "Net-(TOUCH9-TOUCH)") (class "Default")
      (node (ref "R19") (pin "2") (pinfunction "2_2") (pintype "passive"))
      (node (ref "TOUCH9") (pin "PAD") (pinfunction "TOUCH_PAD") (pintype "bidirectional"))
    )
    (net (code "91") (name "Net-(TOUCHHOOK-TOUCH)") (class "Default")
      (node (ref "R21") (pin "2") (pinfunction "2_2") (pintype "passive"))
      (node (ref "TOUCHHOOK") (pin "P$1") (pinfunction "TOUCH_P$1") (pintype "bidirectional"))
    )
    (net (code "92") (name "Net-(U1-EN)") (class "Default")
      (node (ref "U$11") (pin "C") (pinfunction "C_C") (pintype "bidirectional"))
      (node (ref "U1") (pin "3") (pinfunction "EN_3") (pintype "bidirectional"))
    )
    (net (code "93") (name "Net-(U1-VIN)") (class "Default")
      (node (ref "F1") (pin "2") (pinfunction "2_2") (pintype "bidirectional"))
      (node (ref "U$11") (pin "2") (pinfunction "2_2") (pintype "bidirectional"))
      (node (ref "U1") (pin "1") (pinfunction "VIN_1") (pintype "bidirectional"))
    )
    (net (code "94") (name "Net-(U2-PROG)") (class "Default")
      (node (ref "R22") (pin "2") (pinfunction "2_2") (pintype "passive"))
      (node (ref "U2") (pin "5") (pinfunction "PROG_5") (pintype "bidirectional"))
    )
    (net (code "95") (name "Net-(U2-STAT)") (class "Default")
      (node (ref "LED12") (pin "C") (pinfunction "C_C") (pintype "output"))
      (node (ref "U2") (pin "1") (pinfunction "STAT_1") (pintype "bidirectional"))
    )
    (net (code "96") (name "VCC") (class "Default")
      (node (ref "C12") (pin "2") (pinfunction "2_2") (pintype "passive"))
      (node (ref "C13") (pin "2") (pinfunction "2_2") (pintype "passive"))
      (node (ref "C14") (pin "2") (pinfunction "2_2") (pintype "passive"))
      (node (ref "C15") (pin "2") (pinfunction "2_2") (pintype "passive"))
      (node (ref "C16") (pin "2") (pinfunction "2_2") (pintype "passive"))
      (node (ref "C21") (pin "2") (pinfunction "2_2") (pintype "passive"))
      (node (ref "R25") (pin "2") (pinfunction "2_2") (pintype "passive"))
      (node (ref "STLINK") (pin "VCC") (pinfunction "VCC_VCC") (pintype "power_in"))
      (node (ref "U$15") (pin "3.3V") (pinfunction "3.3V_3.3V") (pintype "bidirectional"))
      (node (ref "U$2") (pin "P13") (pinfunction "VDDA_P13") (pintype "bidirectional"))
      (node (ref "U$2") (pin "P19") (pinfunction "VDD4_P19") (pintype "bidirectional"))
      (node (ref "U$2") (pin "P32") (pinfunction "VDD1_P32") (pintype "bidirectional"))
      (node (ref "U$2") (pin "P48") (pinfunction "VDD2_P48") (pintype "bidirectional"))
      (node (ref "U$2") (pin "P64") (pinfunction "VDD3_P64") (pintype "bidirectional"))
      (node (ref "U$22") (pin "VCC") (pinfunction "VCC_VCC") (pintype "bidirectional"))
      (node (ref "U1") (pin "5") (pinfunction "VOUT_5") (pintype "bidirectional"))
      (node (ref "U3") (pin "2") (pinfunction "VS_2") (pintype "bidirectional"))
    )
    (net (code "97") (name "unconnected-(J1-ID-Pad4)") (class "Default")
      (node (ref "J1") (pin "4") (pinfunction "ID_4") (pintype "bidirectional"))
    )
    (net (code "98") (name "unconnected-(U$11-Pad1)") (class "Default")
      (node (ref "U$11") (pin "1") (pinfunction "1_1") (pintype "bidirectional"))
    )
    (net (code "99") (name "unconnected-(U$15-PadDIO2)") (class "Default")
      (node (ref "U$15") (pin "DIO2") (pinfunction "DIO2_DIO2") (pintype "bidirectional"))
    )
    (net (code "100") (name "unconnected-(U$15-PadDIO3)") (class "Default")
      (node (ref "U$15") (pin "DIO3") (pinfunction "DIO3_DIO3") (pintype "bidirectional"))
    )
    (net (code "101") (name "unconnected-(U$15-PadDIO4)") (class "Default")
      (node (ref "U$15") (pin "DIO4") (pinfunction "DIO4_DIO4") (pintype "bidirectional"))
    )
    (net (code "102") (name "unconnected-(U$15-PadDIO5)") (class "Default")
      (node (ref "U$15") (pin "DIO5") (pinfunction "DIO5_DIO5") (pintype "bidirectional"))
    )
  )
)
